# Power4x4r2_Modified.net
KiCad netlist of a schematic drawn in EAGLE
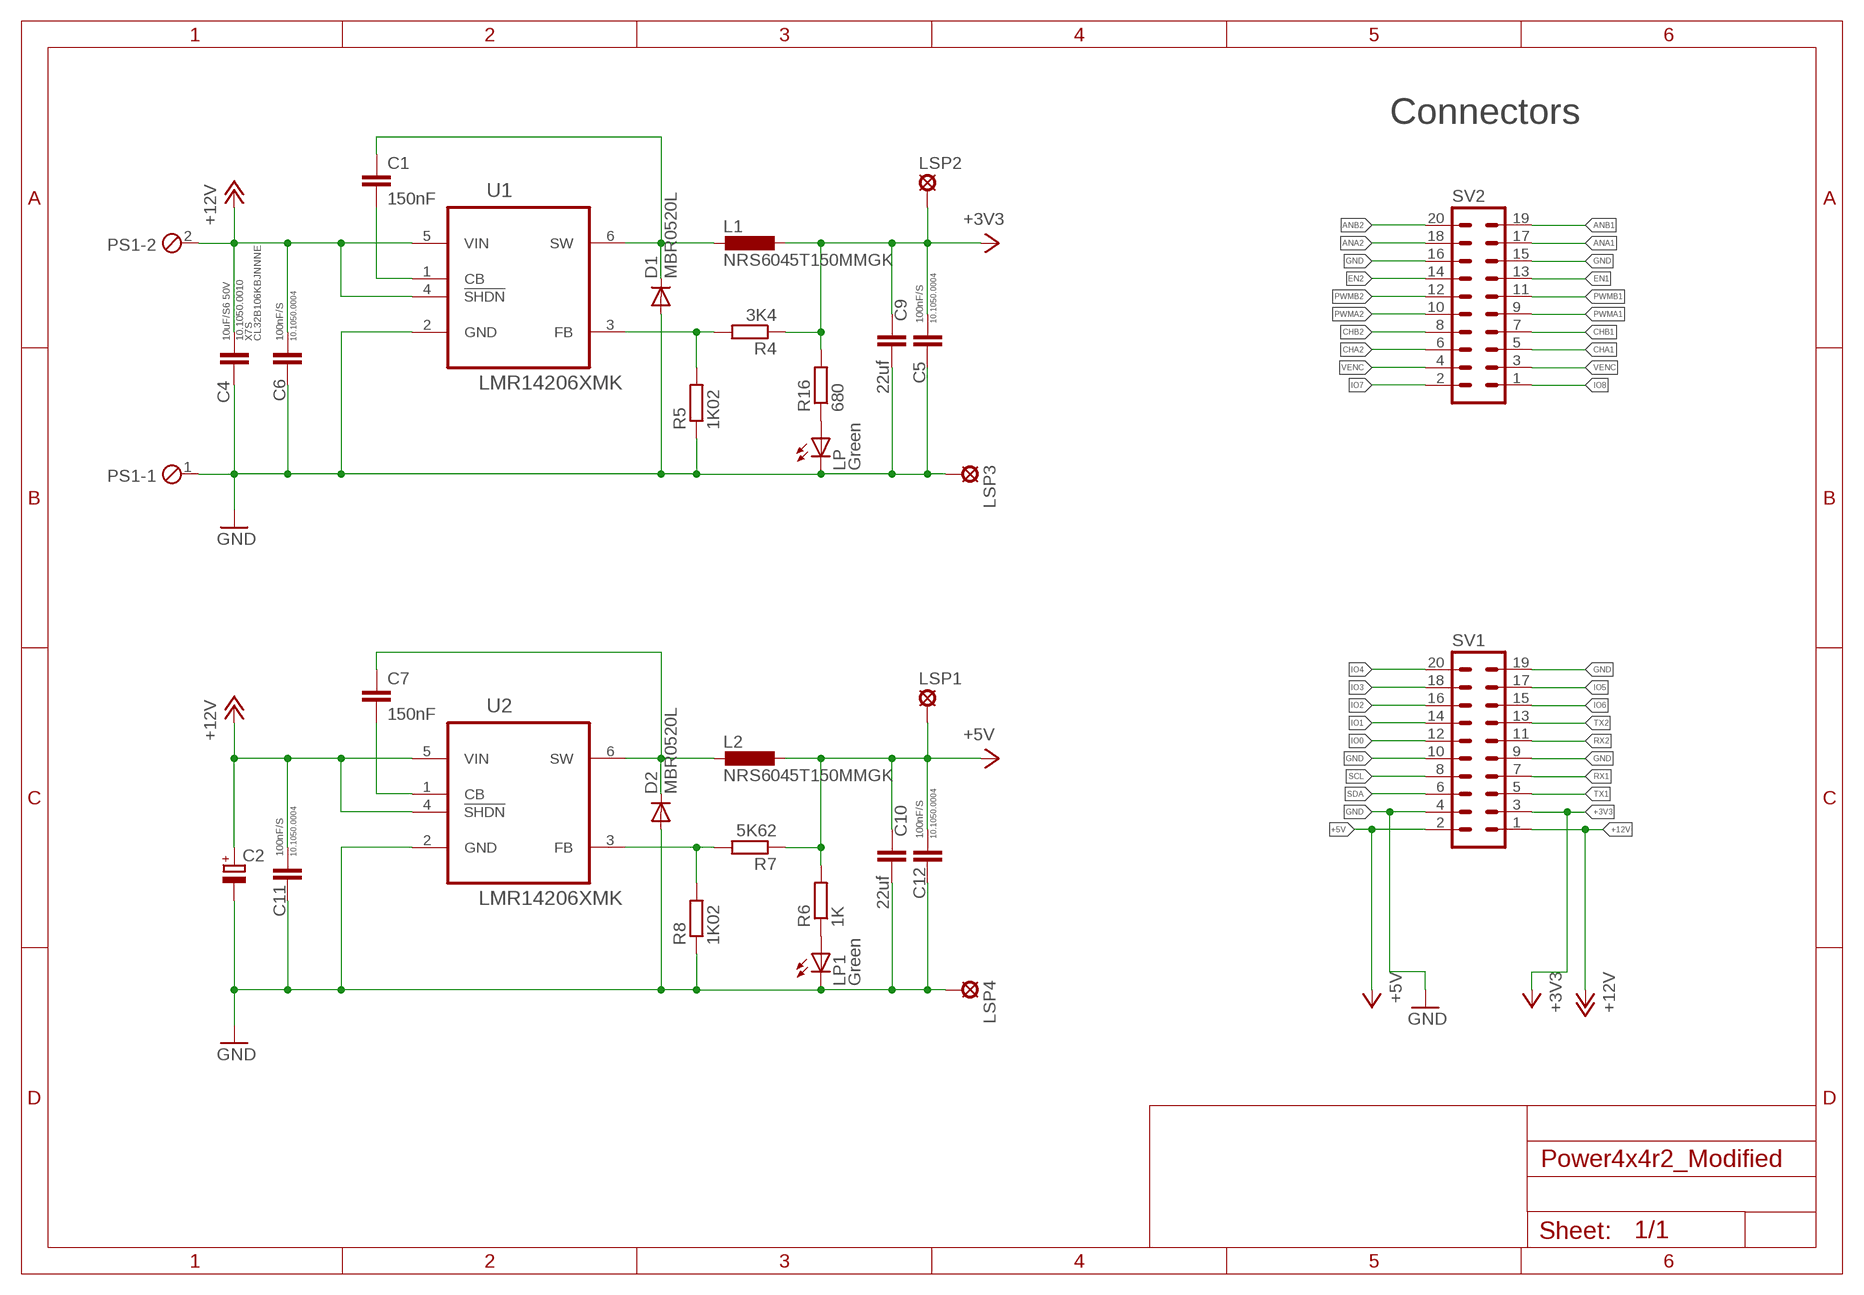
[diagram p0: schematic, sheet 1]

(export (version "E")
  (design (tool "Eeschema 10.0.6"))
  (components
    (comp (ref "C1")
      (value "150nF")
      (footprint "eagle-import:C0805K")
      (libsource (lib "eagle-import") (part "C-EUC0805K"))
    )
    (comp (ref "C2")
      (value "CPOL-EUUD-6,3X7,7")
      (footprint "eagle-import:UD-6,3X7,7_NICHICON")
      (libsource (lib "eagle-import") (part "CPOL-EUUD-6,3X7,7"))
    )
    (comp (ref "C4")
      (value "10uF/S6 50V")
      (footprint "eagle-import:C3225")
      (fields
        (field (name "CODE") "CL32B106KBJNNNE")
        (field (name "KATODO") "10.1050.0010")
        (field (name "TEMPERATURE") "X7S")
      )
      (libsource (lib "eagle-import") (part "C-EUC3225"))
    )
    (comp (ref "C5")
      (value "100nF/S")
      (footprint "eagle-import:C0805")
      (fields (field (name "KATODO") "10.1050.0004"))
      (libsource (lib "eagle-import") (part "C-EUC0805"))
    )
    (comp (ref "C6")
      (value "100nF/S")
      (footprint "eagle-import:C0805")
      (fields (field (name "KATODO") "10.1050.0004"))
      (libsource (lib "eagle-import") (part "C-EUC0805"))
    )
    (comp (ref "C7")
      (value "150nF")
      (footprint "eagle-import:C0805K")
      (libsource (lib "eagle-import") (part "C-EUC0805K"))
    )
    (comp (ref "C9")
      (value "22uf")
      (footprint "eagle-import:C1206")
      (libsource (lib "eagle-import") (part "C-EUC1206"))
    )
    (comp (ref "C10")
      (value "22uf")
      (footprint "eagle-import:C1206")
      (libsource (lib "eagle-import") (part "C-EUC1206"))
    )
    (comp (ref "C11")
      (value "100nF/S")
      (footprint "eagle-import:C0805")
      (fields (field (name "KATODO") "10.1050.0004"))
      (libsource (lib "eagle-import") (part "C-EUC0805"))
    )
    (comp (ref "C12")
      (value "100nF/S")
      (footprint "eagle-import:C0805")
      (fields (field (name "KATODO") "10.1050.0004"))
      (libsource (lib "eagle-import") (part "C-EUC0805"))
    )
    (comp (ref "D1")
      (value "MBR0520L")
      (footprint "eagle-import:SOD123")
      (libsource (lib "eagle-import") (part "DIODE-SOD123"))
    )
    (comp (ref "D2")
      (value "MBR0520L")
      (footprint "eagle-import:SOD123")
      (libsource (lib "eagle-import") (part "DIODE-SOD123"))
    )
    (comp (ref "L1")
      (value "NRS6045T150MMGK")
      (footprint "eagle-import:POWER-CHOKE_WE-TPC")
      (libsource (lib "eagle-import") (part "L-EUWE-TPC"))
    )
    (comp (ref "L2")
      (value "NRS6045T150MMGK")
      (footprint "eagle-import:POWER-CHOKE_WE-TPC")
      (libsource (lib "eagle-import") (part "L-EUWE-TPC"))
    )
    (comp (ref "LP")
      (value "Green")
      (footprint "eagle-import:CHIPLED_0805")
      (libsource (lib "eagle-import") (part "LEDCHIPLED_0805"))
    )
    (comp (ref "LP1")
      (value "Green")
      (footprint "eagle-import:CHIPLED_0805")
      (libsource (lib "eagle-import") (part "LEDCHIPLED_0805"))
    )
    (comp (ref "LSP1")
      (value "LSP10")
      (footprint "eagle-import:LSP10")
      (libsource (lib "eagle-import") (part "LSP10"))
    )
    (comp (ref "LSP2")
      (value "LSP10")
      (footprint "eagle-import:LSP10")
      (libsource (lib "eagle-import") (part "LSP10"))
    )
    (comp (ref "LSP3")
      (value "LSP10")
      (footprint "eagle-import:LSP10")
      (libsource (lib "eagle-import") (part "LSP10"))
    )
    (comp (ref "LSP4")
      (value "LSP10")
      (footprint "eagle-import:LSP10")
      (libsource (lib "eagle-import") (part "LSP10"))
    )
    (comp (ref "PS1")
      (value "MPT2")
      (footprint "eagle-import:2POL254")
      (libsource (lib "eagle-import") (part "MPT2"))
    )
    (comp (ref "R4")
      (value "3K4")
      (footprint "eagle-import:R0805")
      (libsource (lib "eagle-import") (part "R-EU_R0805"))
    )
    (comp (ref "R5")
      (value "1K02")
      (footprint "eagle-import:R0805")
      (libsource (lib "eagle-import") (part "R-EU_R0805"))
    )
    (comp (ref "R6")
      (value "1K")
      (footprint "eagle-import:R0603")
      (libsource (lib "eagle-import") (part "R-EU_R0603"))
    )
    (comp (ref "R7")
      (value "5K62")
      (footprint "eagle-import:R0805")
      (libsource (lib "eagle-import") (part "R-EU_R0805"))
    )
    (comp (ref "R8")
      (value "1K02")
      (footprint "eagle-import:R0805")
      (libsource (lib "eagle-import") (part "R-EU_R0805"))
    )
    (comp (ref "R16")
      (value "680")
      (footprint "eagle-import:R0603")
      (libsource (lib "eagle-import") (part "R-EU_R0603"))
    )
    (comp (ref "SV1")
      (value "MA10-2")
      (footprint "eagle-import:MA10-2")
      (libsource (lib "eagle-import") (part "MA10-2"))
    )
    (comp (ref "SV2")
      (value "MA10-2")
      (footprint "eagle-import:MA10-2")
      (fields (field (name "OC_FARNELL") "unknown") (field (name "OC_NEWARK") "unknown"))
      (libsource (lib "eagle-import") (part "MA10-2"))
    )
    (comp (ref "U1")
      (value "LMR14206XMK")
      (footprint "eagle-import:SOT95P280X110-6N")
      (libsource (lib "eagle-import") (part "LMR14206XMK"))
    )
    (comp (ref "U2")
      (value "LMR14206XMK")
      (footprint "eagle-import:SOT95P280X110-6N")
      (libsource (lib "eagle-import") (part "LMR14206XMK"))
    )
  )
  (nets
    (net (code "1") (name "+3V3") (class "Default")
      (node (ref "C5") (pin "2") (pinfunction "2_2") (pintype "passive"))
      (node (ref "C9") (pin "1") (pinfunction "1_1") (pintype "passive"))
      (node (ref "L1") (pin "1") (pinfunction "1_1") (pintype "passive"))
      (node (ref "LSP2") (pin "MP") (pinfunction "MP_MP") (pintype "passive"))
      (node (ref "R16") (pin "2") (pinfunction "2_2") (pintype "passive"))
      (node (ref "R4") (pin "1") (pinfunction "1_1") (pintype "passive"))
      (node (ref "SV1") (pin "3") (pinfunction "3_3") (pintype "passive"))
    )
    (net (code "2") (name "+5V") (class "Default")
      (node (ref "C10") (pin "1") (pinfunction "1_1") (pintype "passive"))
      (node (ref "C12") (pin "2") (pinfunction "2_2") (pintype "passive"))
      (node (ref "L2") (pin "1") (pinfunction "1_1") (pintype "passive"))
      (node (ref "LSP1") (pin "MP") (pinfunction "MP_MP") (pintype "passive"))
      (node (ref "R6") (pin "2") (pinfunction "2_2") (pintype "passive"))
      (node (ref "R7") (pin "1") (pinfunction "1_1") (pintype "passive"))
      (node (ref "SV1") (pin "2") (pinfunction "2_2") (pintype "passive"))
    )
    (net (code "3") (name "+12V") (class "Default")
      (node (ref "C11") (pin "2") (pinfunction "2_2") (pintype "passive"))
      (node (ref "C2") (pin "+") (pinfunction "+_+") (pintype "passive"))
      (node (ref "C4") (pin "1") (pinfunction "1_1") (pintype "passive"))
      (node (ref "C6") (pin "2") (pinfunction "2_2") (pintype "passive"))
      (node (ref "PS1") (pin "2") (pinfunction "1_2") (pintype "passive"))
      (node (ref "SV1") (pin "1") (pinfunction "1_1") (pintype "passive"))
      (node (ref "U1") (pin "4") (pinfunction "~{SHDN}_4") (pintype "input"))
      (node (ref "U1") (pin "5") (pinfunction "VIN_5") (pintype "power_in"))
      (node (ref "U2") (pin "4") (pinfunction "~{SHDN}_4") (pintype "input"))
      (node (ref "U2") (pin "5") (pinfunction "VIN_5") (pintype "power_in"))
    )
    (net (code "4") (name "ANA1") (class "Default")
      (node (ref "SV2") (pin "17") (pinfunction "17_17") (pintype "passive"))
    )
    (net (code "5") (name "ANA2") (class "Default")
      (node (ref "SV2") (pin "18") (pinfunction "18_18") (pintype "passive"))
    )
    (net (code "6") (name "ANB1") (class "Default")
      (node (ref "SV2") (pin "19") (pinfunction "19_19") (pintype "passive"))
    )
    (net (code "7") (name "ANB2") (class "Default")
      (node (ref "SV2") (pin "20") (pinfunction "20_20") (pintype "passive"))
    )
    (net (code "8") (name "CHA1") (class "Default")
      (node (ref "SV2") (pin "5") (pinfunction "5_5") (pintype "passive"))
    )
    (net (code "9") (name "CHA2") (class "Default")
      (node (ref "SV2") (pin "6") (pinfunction "6_6") (pintype "passive"))
    )
    (net (code "10") (name "CHB1") (class "Default")
      (node (ref "SV2") (pin "7") (pinfunction "7_7") (pintype "passive"))
    )
    (net (code "11") (name "CHB2") (class "Default")
      (node (ref "SV2") (pin "8") (pinfunction "8_8") (pintype "passive"))
    )
    (net (code "12") (name "EN1") (class "Default")
      (node (ref "SV2") (pin "13") (pinfunction "13_13") (pintype "passive"))
    )
    (net (code "13") (name "EN2") (class "Default")
      (node (ref "SV2") (pin "14") (pinfunction "14_14") (pintype "passive"))
    )
    (net (code "14") (name "GND") (class "Default")
      (node (ref "C10") (pin "2") (pinfunction "2_2") (pintype "passive"))
      (node (ref "C11") (pin "1") (pinfunction "1_1") (pintype "passive"))
      (node (ref "C12") (pin "1") (pinfunction "1_1") (pintype "passive"))
      (node (ref "C2") (pin "-") (pinfunction "-_-") (pintype "passive"))
      (node (ref "C4") (pin "2") (pinfunction "2_2") (pintype "passive"))
      (node (ref "C5") (pin "1") (pinfunction "1_1") (pintype "passive"))
      (node (ref "C6") (pin "1") (pinfunction "1_1") (pintype "passive"))
      (node (ref "C9") (pin "2") (pinfunction "2_2") (pintype "passive"))
      (node (ref "D1") (pin "A") (pinfunction "A_A") (pintype "passive"))
      (node (ref "D2") (pin "A") (pinfunction "A_A") (pintype "passive"))
      (node (ref "LP") (pin "C") (pinfunction "C_C") (pintype "passive"))
      (node (ref "LP1") (pin "C") (pinfunction "C_C") (pintype "passive"))
      (node (ref "LSP3") (pin "MP") (pinfunction "MP_MP") (pintype "passive"))
      (node (ref "LSP4") (pin "MP") (pinfunction "MP_MP") (pintype "passive"))
      (node (ref "PS1") (pin "1") (pinfunction "1_1") (pintype "passive"))
      (node (ref "R5") (pin "1") (pinfunction "1_1") (pintype "passive"))
      (node (ref "R8") (pin "1") (pinfunction "1_1") (pintype "passive"))
      (node (ref "SV1") (pin "10") (pinfunction "10_10") (pintype "passive"))
      (node (ref "SV1") (pin "19") (pinfunction "19_19") (pintype "passive"))
      (node (ref "SV1") (pin "4") (pinfunction "4_4") (pintype "passive"))
      (node (ref "SV1") (pin "9") (pinfunction "9_9") (pintype "passive"))
      (node (ref "SV2") (pin "15") (pinfunction "15_15") (pintype "passive"))
      (node (ref "SV2") (pin "16") (pinfunction "16_16") (pintype "passive"))
      (node (ref "U1") (pin "2") (pinfunction "GND_2") (pintype "passive"))
      (node (ref "U2") (pin "2") (pinfunction "GND_2") (pintype "passive"))
    )
    (net (code "15") (name "IO0") (class "Default")
      (node (ref "SV1") (pin "12") (pinfunction "12_12") (pintype "passive"))
    )
    (net (code "16") (name "IO1") (class "Default")
      (node (ref "SV1") (pin "14") (pinfunction "14_14") (pintype "passive"))
    )
    (net (code "17") (name "IO2") (class "Default")
      (node (ref "SV1") (pin "16") (pinfunction "16_16") (pintype "passive"))
    )
    (net (code "18") (name "IO3") (class "Default")
      (node (ref "SV1") (pin "18") (pinfunction "18_18") (pintype "passive"))
    )
    (net (code "19") (name "IO4") (class "Default")
      (node (ref "SV1") (pin "20") (pinfunction "20_20") (pintype "passive"))
    )
    (net (code "20") (name "IO5") (class "Default")
      (node (ref "SV1") (pin "17") (pinfunction "17_17") (pintype "passive"))
    )
    (net (code "21") (name "IO6") (class "Default")
      (node (ref "SV1") (pin "15") (pinfunction "15_15") (pintype "passive"))
    )
    (net (code "22") (name "IO7") (class "Default")
      (node (ref "SV2") (pin "2") (pinfunction "2_2") (pintype "passive"))
    )
    (net (code "23") (name "IO8") (class "Default")
      (node (ref "SV2") (pin "1") (pinfunction "1_1") (pintype "passive"))
    )
    (net (code "24") (name "Net-(LP-PadA)") (class "Default")
      (node (ref "LP") (pin "A") (pinfunction "A_A") (pintype "passive"))
      (node (ref "R16") (pin "1") (pinfunction "1_1") (pintype "passive"))
    )
    (net (code "25") (name "Net-(LP1-PadA)") (class "Default")
      (node (ref "LP1") (pin "A") (pinfunction "A_A") (pintype "passive"))
      (node (ref "R6") (pin "1") (pinfunction "1_1") (pintype "passive"))
    )
    (net (code "26") (name "Net-(U1-CB)") (class "Default")
      (node (ref "C1") (pin "2") (pinfunction "2_2") (pintype "passive"))
      (node (ref "U1") (pin "1") (pinfunction "CB_1") (pintype "passive"))
    )
    (net (code "27") (name "Net-(U1-FB)") (class "Default")
      (node (ref "R4") (pin "2") (pinfunction "2_2") (pintype "passive"))
      (node (ref "R5") (pin "2") (pinfunction "2_2") (pintype "passive"))
      (node (ref "U1") (pin "3") (pinfunction "FB_3") (pintype "input"))
    )
    (net (code "28") (name "Net-(U1-SW)") (class "Default")
      (node (ref "C1") (pin "1") (pinfunction "1_1") (pintype "passive"))
      (node (ref "D1") (pin "C") (pinfunction "C_C") (pintype "passive"))
      (node (ref "L1") (pin "2") (pinfunction "2_2") (pintype "passive"))
      (node (ref "U1") (pin "6") (pinfunction "SW_6") (pintype "output"))
    )
    (net (code "29") (name "Net-(U2-CB)") (class "Default")
      (node (ref "C7") (pin "2") (pinfunction "2_2") (pintype "passive"))
      (node (ref "U2") (pin "1") (pinfunction "CB_1") (pintype "passive"))
    )
    (net (code "30") (name "Net-(U2-FB)") (class "Default")
      (node (ref "R7") (pin "2") (pinfunction "2_2") (pintype "passive"))
      (node (ref "R8") (pin "2") (pinfunction "2_2") (pintype "passive"))
      (node (ref "U2") (pin "3") (pinfunction "FB_3") (pintype "input"))
    )
    (net (code "31") (name "Net-(U2-SW)") (class "Default")
      (node (ref "C7") (pin "1") (pinfunction "1_1") (pintype "passive"))
      (node (ref "D2") (pin "C") (pinfunction "C_C") (pintype "passive"))
      (node (ref "L2") (pin "2") (pinfunction "2_2") (pintype "passive"))
      (node (ref "U2") (pin "6") (pinfunction "SW_6") (pintype "output"))
    )
    (net (code "32") (name "PWMA1") (class "Default")
      (node (ref "SV2") (pin "9") (pinfunction "9_9") (pintype "passive"))
    )
    (net (code "33") (name "PWMA2") (class "Default")
      (node (ref "SV2") (pin "10") (pinfunction "10_10") (pintype "passive"))
    )
    (net (code "34") (name "PWMB1") (class "Default")
      (node (ref "SV2") (pin "11") (pinfunction "11_11") (pintype "passive"))
    )
    (net (code "35") (name "PWMB2") (class "Default")
      (node (ref "SV2") (pin "12") (pinfunction "12_12") (pintype "passive"))
    )
    (net (code "36") (name "RX1") (class "Default")
      (node (ref "SV1") (pin "7") (pinfunction "7_7") (pintype "passive"))
    )
    (net (code "37") (name "RX2") (class "Default")
      (node (ref "SV1") (pin "11") (pinfunction "11_11") (pintype "passive"))
    )
    (net (code "38") (name "SCL") (class "Default")
      (node (ref "SV1") (pin "8") (pinfunction "8_8") (pintype "passive"))
    )
    (net (code "39") (name "SDA") (class "Default")
      (node (ref "SV1") (pin "6") (pinfunction "6_6") (pintype "passive"))
    )
    (net (code "40") (name "TX1") (class "Default")
      (node (ref "SV1") (pin "5") (pinfunction "5_5") (pintype "passive"))
    )
    (net (code "41") (name "TX2") (class "Default")
      (node (ref "SV1") (pin "13") (pinfunction "13_13") (pintype "passive"))
    )
    (net (code "42") (name "VENC") (class "Default")
      (node (ref "SV2") (pin "3") (pinfunction "3_3") (pintype "passive"))
      (node (ref "SV2") (pin "4") (pinfunction "4_4") (pintype "passive"))
    )
  )
)
